# atmel_midi_cv_2layer.net
KiCad netlist of a schematic drawn in EAGLE
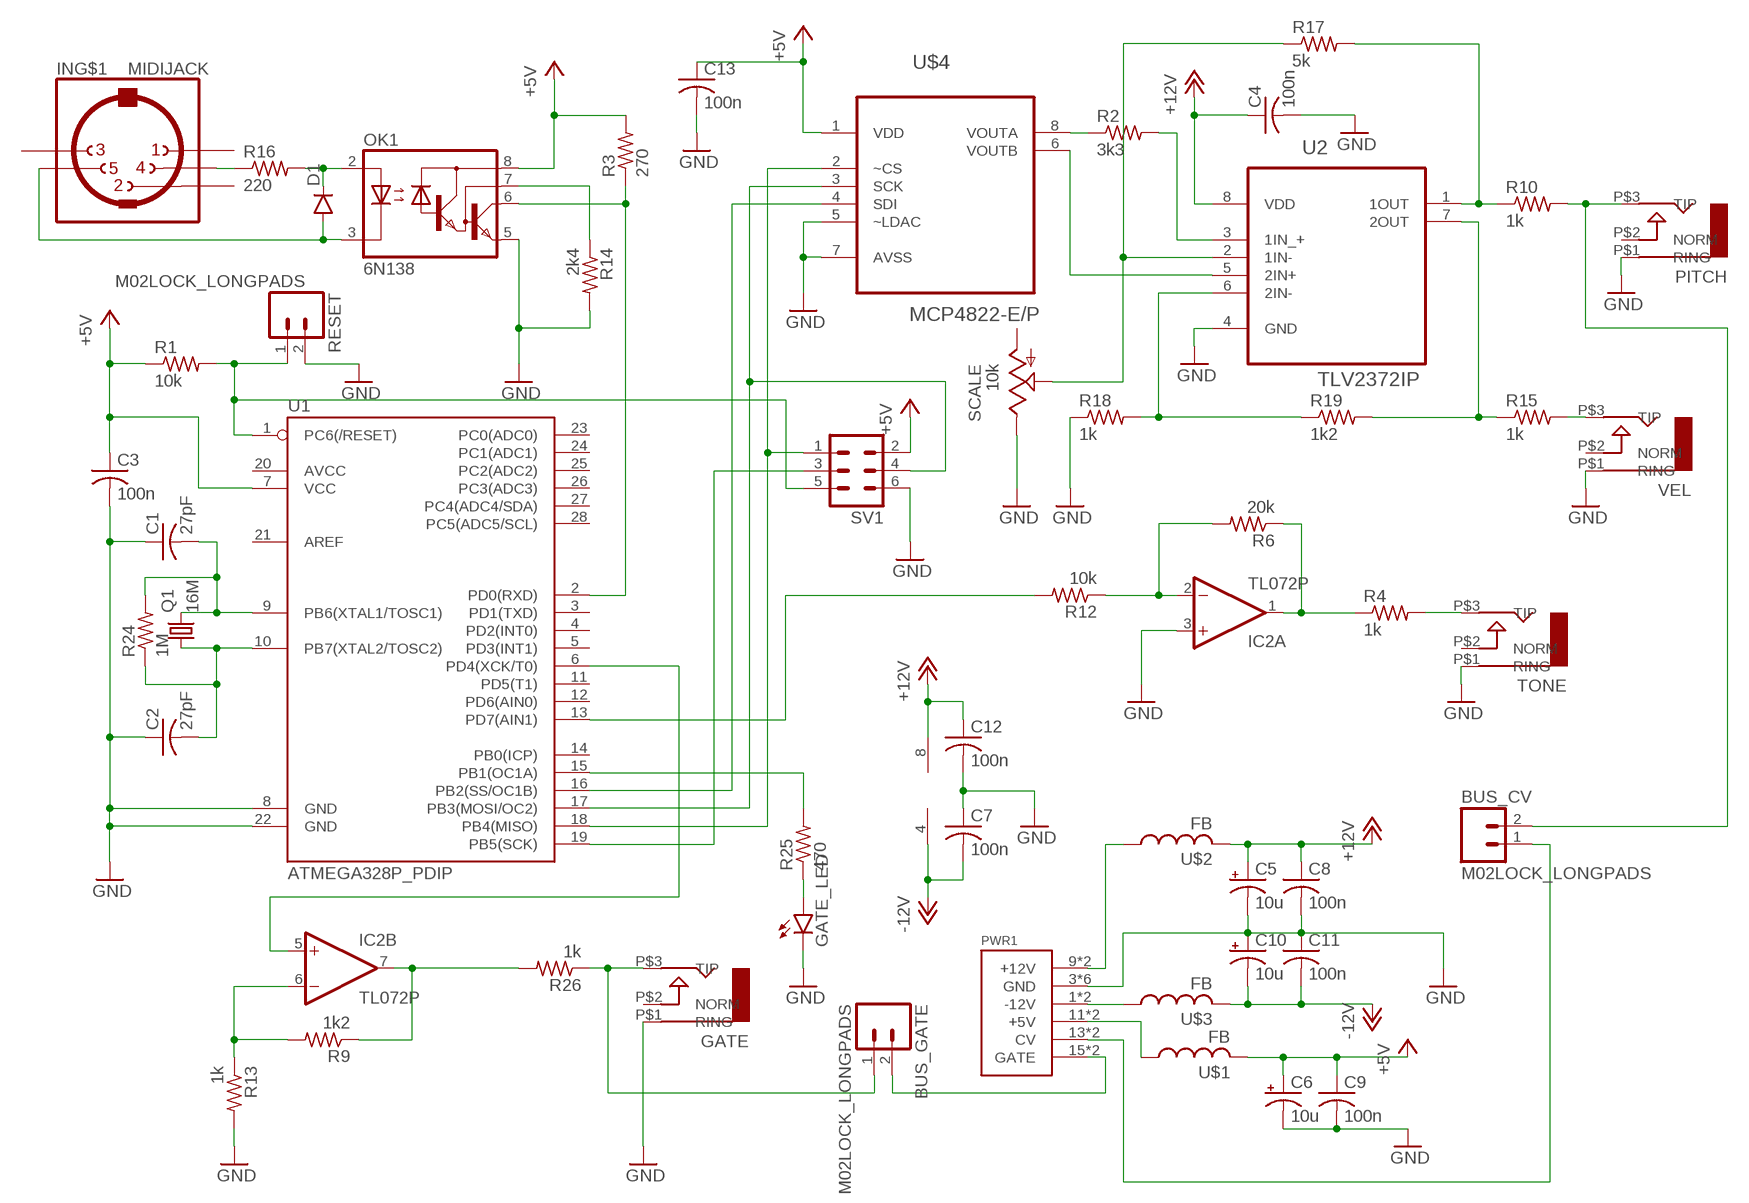
[diagram p0: schematic, sheet 1]

(export (version "E")
  (design (tool "Eeschema 10.0.6"))
  (components
    (comp (ref "BUS_CV")
      (value "M02LOCK_LONGPADS")
      (footprint "eagle-import:1X02_LOCK_LONGPADS")
      (libsource (lib "eagle-import") (part "M02LOCK_LONGPADS"))
    )
    (comp (ref "BUS_GATE")
      (value "M02LOCK_LONGPADS")
      (footprint "eagle-import:1X02_LOCK_LONGPADS")
      (libsource (lib "eagle-import") (part "M02LOCK_LONGPADS"))
    )
    (comp (ref "C1")
      (value "27pF")
      (footprint "eagle-import:C025-040X050")
      (libsource (lib "eagle-import") (part "C-US025-040X050"))
    )
    (comp (ref "C2")
      (value "27pF")
      (footprint "eagle-import:C025-040X050")
      (libsource (lib "eagle-import") (part "C-US025-040X050"))
    )
    (comp (ref "C3")
      (value "100n")
      (footprint "eagle-import:C050-024X044")
      (libsource (lib "eagle-import") (part "C-US050-024X044"))
    )
    (comp (ref "C4")
      (value "100n")
      (footprint "eagle-import:C050-024X044")
      (libsource (lib "eagle-import") (part "C-US050-024X044"))
    )
    (comp (ref "C5")
      (value "10u")
      (footprint "eagle-import:B45181A")
      (libsource (lib "eagle-import") (part "CPOL-USB45181A"))
    )
    (comp (ref "C6")
      (value "10u")
      (footprint "eagle-import:B45181A")
      (libsource (lib "eagle-import") (part "CPOL-USB45181A"))
    )
    (comp (ref "C7")
      (value "100n")
      (footprint "eagle-import:C050-024X044")
      (libsource (lib "eagle-import") (part "C-US050-024X044"))
    )
    (comp (ref "C8")
      (value "100n")
      (footprint "eagle-import:C050-024X044")
      (libsource (lib "eagle-import") (part "C-US050-024X044"))
    )
    (comp (ref "C9")
      (value "100n")
      (footprint "eagle-import:C050-024X044")
      (libsource (lib "eagle-import") (part "C-US050-024X044"))
    )
    (comp (ref "C10")
      (value "10u")
      (footprint "eagle-import:B45181A")
      (libsource (lib "eagle-import") (part "CPOL-USB45181A"))
    )
    (comp (ref "C11")
      (value "100n")
      (footprint "eagle-import:C050-024X044")
      (libsource (lib "eagle-import") (part "C-US050-024X044"))
    )
    (comp (ref "C12")
      (value "100n")
      (footprint "eagle-import:C050-024X044")
      (libsource (lib "eagle-import") (part "C-US050-024X044"))
    )
    (comp (ref "C13")
      (value "100n")
      (footprint "eagle-import:C050-024X044")
      (libsource (lib "eagle-import") (part "C-US050-024X044"))
    )
    (comp (ref "D1")
      (value "DIODE1N4148")
      (footprint "eagle-import:DIODE-1N4148")
      (libsource (lib "eagle-import") (part "DIODE1N4148"))
    )
    (comp (ref "GATE")
      (value "AUDIO-JACKITEAD")
      (footprint "eagle-import:JACK-90DEG-ITEAD")
      (libsource (lib "eagle-import") (part "AUDIO-JACKITEAD"))
    )
    (comp (ref "GATE_LED")
      (value "LED3MM")
      (footprint "eagle-import:LED3MM")
      (libsource (lib "eagle-import") (part "LED3MM"))
    )
    (comp (ref "IC2")
      (value "TL072P")
      (footprint "eagle-import:DIL08")
      (libsource (lib "eagle-import") (part "TL072P"))
    )
    (comp (ref "IN")
      (value "MIDIJACK")
      (footprint "eagle-import:CP-2350")
      (libsource (lib "eagle-import") (part "MIDIJACK"))
    )
    (comp (ref "OK1")
      (value "6N138")
      (footprint "eagle-import:DIL08")
      (fields (field (name "MF") "VISHAY/TELEFUNKEN"))
      (libsource (lib "eagle-import") (part "6N138"))
    )
    (comp (ref "PITCH")
      (value "AUDIO-JACKITEAD")
      (footprint "eagle-import:JACK-90DEG-ITEAD")
      (libsource (lib "eagle-import") (part "AUDIO-JACKITEAD"))
    )
    (comp (ref "PWR1")
      (value "POWER")
      (footprint "eagle-import:POWER_16")
      (libsource (lib "eagle-import") (part "POWER"))
    )
    (comp (ref "Q1")
      (value "16M")
      (footprint "eagle-import:HC49_S")
      (libsource (lib "eagle-import") (part "CRYSTALHC49S"))
    )
    (comp (ref "R1")
      (value "10k")
      (footprint "eagle-import:0207_7")
      (libsource (lib "eagle-import") (part "R-US_0207/7"))
    )
    (comp (ref "R2")
      (value "3k3")
      (footprint "eagle-import:0207_7")
      (libsource (lib "eagle-import") (part "R-US_0207/7"))
    )
    (comp (ref "R3")
      (value "270")
      (footprint "eagle-import:0207_7")
      (libsource (lib "eagle-import") (part "R-US_0207/7"))
    )
    (comp (ref "R4")
      (value "1k")
      (footprint "eagle-import:0207_7")
      (libsource (lib "eagle-import") (part "R-US_0207/7"))
    )
    (comp (ref "R6")
      (value "20k")
      (footprint "eagle-import:0207_7")
      (libsource (lib "eagle-import") (part "R-US_0207/7"))
    )
    (comp (ref "R9")
      (value "1k2")
      (footprint "eagle-import:0207_7")
      (libsource (lib "eagle-import") (part "R-US_0207/7"))
    )
    (comp (ref "R10")
      (value "1k")
      (footprint "eagle-import:0207_7")
      (libsource (lib "eagle-import") (part "R-US_0207/7"))
    )
    (comp (ref "R12")
      (value "10k")
      (footprint "eagle-import:0207_7")
      (libsource (lib "eagle-import") (part "R-US_0207/7"))
    )
    (comp (ref "R13")
      (value "1k")
      (footprint "eagle-import:0207_7")
      (libsource (lib "eagle-import") (part "R-US_0207/7"))
    )
    (comp (ref "R14")
      (value "2k4")
      (footprint "eagle-import:0207_7")
      (libsource (lib "eagle-import") (part "R-US_0207/7"))
    )
    (comp (ref "R15")
      (value "1k")
      (footprint "eagle-import:0207_7")
      (libsource (lib "eagle-import") (part "R-US_0207/7"))
    )
    (comp (ref "R16")
      (value "220")
      (footprint "eagle-import:0207_7")
      (libsource (lib "eagle-import") (part "R-US_0207/7"))
    )
    (comp (ref "R17")
      (value "5k")
      (footprint "eagle-import:0207_7")
      (libsource (lib "eagle-import") (part "R-US_0207/7"))
    )
    (comp (ref "R18")
      (value "1k")
      (footprint "eagle-import:0207_7")
      (libsource (lib "eagle-import") (part "R-US_0207/7"))
    )
    (comp (ref "R19")
      (value "1k2")
      (footprint "eagle-import:0207_7")
      (libsource (lib "eagle-import") (part "R-US_0207/7"))
    )
    (comp (ref "R24")
      (value "1M")
      (footprint "eagle-import:0207_7")
      (libsource (lib "eagle-import") (part "R-US_0207/7"))
    )
    (comp (ref "R25")
      (value "470")
      (footprint "eagle-import:0207_7")
      (libsource (lib "eagle-import") (part "R-US_0207/7"))
    )
    (comp (ref "R26")
      (value "1k")
      (footprint "eagle-import:0207_7")
      (libsource (lib "eagle-import") (part "R-US_0207/7"))
    )
    (comp (ref "RESET")
      (value "M02LOCK_LONGPADS")
      (footprint "eagle-import:1X02_LOCK_LONGPADS")
      (libsource (lib "eagle-import") (part "M02LOCK_LONGPADS"))
    )
    (comp (ref "SCALE")
      (value "10k")
      (footprint "eagle-import:B64W")
      (libsource (lib "eagle-import") (part "TRIM_US-B64W"))
    )
    (comp (ref "SV1")
      (value "MA03-2")
      (footprint "eagle-import:MA03-2")
      (libsource (lib "eagle-import") (part "MA03-2"))
    )
    (comp (ref "TONE")
      (value "AUDIO-JACKITEAD")
      (footprint "eagle-import:JACK-90DEG-ITEAD")
      (libsource (lib "eagle-import") (part "AUDIO-JACKITEAD"))
    )
    (comp (ref "U$1") (value "FB") (footprint "eagle-import:FB") (libsource (lib "eagle-import") (part "FB")))
    (comp (ref "U$2") (value "FB") (footprint "eagle-import:FB") (libsource (lib "eagle-import") (part "FB")))
    (comp (ref "U$3") (value "FB") (footprint "eagle-import:FB") (libsource (lib "eagle-import") (part "FB")))
    (comp (ref "U$4")
      (value "MCP4822-E/P")
      (footprint "eagle-import:DIP254P762X432-8")
      (libsource (lib "eagle-import") (part "MCP4822-E/P"))
    )
    (comp (ref "U1")
      (value "ATMEGA328P_PDIP")
      (footprint "eagle-import:DIL28-3")
      (libsource (lib "eagle-import") (part "ATMEGA328P_PDIP"))
    )
    (comp (ref "U2")
      (value "TLV2372IP")
      (footprint "eagle-import:DIP254P762X508-8")
      (libsource (lib "eagle-import") (part "TLV2372IP"))
    )
    (comp (ref "VEL")
      (value "AUDIO-JACKITEAD")
      (footprint "eagle-import:JACK-90DEG-ITEAD")
      (libsource (lib "eagle-import") (part "AUDIO-JACKITEAD"))
    )
  )
  (nets
    (net (code "1") (name "+5V") (class "Default")
      (node (ref "C13") (pin "1") (pinfunction "1_1") (pintype "passive"))
      (node (ref "C3") (pin "1") (pinfunction "1_1") (pintype "passive"))
      (node (ref "C6") (pin "+") (pinfunction "+_+") (pintype "passive"))
      (node (ref "C9") (pin "1") (pinfunction "1_1") (pintype "passive"))
      (node (ref "OK1") (pin "8") (pinfunction "VCC_8") (pintype "passive"))
      (node (ref "R1") (pin "1") (pinfunction "1_1") (pintype "passive"))
      (node (ref "R3") (pin "2") (pinfunction "2_2") (pintype "passive"))
      (node (ref "SV1") (pin "2") (pinfunction "2_2") (pintype "passive"))
      (node (ref "U$1") (pin "P$2") (pinfunction "2_P$2") (pintype "passive"))
      (node (ref "U$4") (pin "1") (pinfunction "VDD_1") (pintype "power_in"))
      (node (ref "U1") (pin "7") (pinfunction "VCC_7") (pintype "bidirectional"))
    )
    (net (code "2") (name "+12V") (class "Default")
      (node (ref "C12") (pin "1") (pinfunction "1_1") (pintype "passive"))
      (node (ref "C4") (pin "1") (pinfunction "1_1") (pintype "passive"))
      (node (ref "C5") (pin "+") (pinfunction "+_+") (pintype "passive"))
      (node (ref "C8") (pin "1") (pinfunction "1_1") (pintype "passive"))
      (node (ref "IC2") (pin "8") (pinfunction "V+_8") (pintype "power_in"))
      (node (ref "U$2") (pin "P$2") (pinfunction "2_P$2") (pintype "passive"))
      (node (ref "U2") (pin "8") (pinfunction "VDD_8") (pintype "power_in"))
    )
    (net (code "3") (name "-12V") (class "Default")
      (node (ref "C10") (pin "-") (pinfunction "-_-") (pintype "passive"))
      (node (ref "C11") (pin "2") (pinfunction "2_2") (pintype "passive"))
      (node (ref "C7") (pin "2") (pinfunction "2_2") (pintype "passive"))
      (node (ref "IC2") (pin "4") (pinfunction "V-_4") (pintype "power_in"))
      (node (ref "U$3") (pin "P$2") (pinfunction "2_P$2") (pintype "passive"))
    )
    (net (code "4") (name "GND") (class "Default")
      (node (ref "C1") (pin "1") (pinfunction "1_1") (pintype "passive"))
      (node (ref "C10") (pin "+") (pinfunction "+_+") (pintype "passive"))
      (node (ref "C11") (pin "1") (pinfunction "1_1") (pintype "passive"))
      (node (ref "C12") (pin "2") (pinfunction "2_2") (pintype "passive"))
      (node (ref "C13") (pin "2") (pinfunction "2_2") (pintype "passive"))
      (node (ref "C2") (pin "1") (pinfunction "1_1") (pintype "passive"))
      (node (ref "C3") (pin "2") (pinfunction "2_2") (pintype "passive"))
      (node (ref "C4") (pin "2") (pinfunction "2_2") (pintype "passive"))
      (node (ref "C5") (pin "-") (pinfunction "-_-") (pintype "passive"))
      (node (ref "C6") (pin "-") (pinfunction "-_-") (pintype "passive"))
      (node (ref "C7") (pin "1") (pinfunction "1_1") (pintype "passive"))
      (node (ref "C8") (pin "2") (pinfunction "2_2") (pintype "passive"))
      (node (ref "C9") (pin "2") (pinfunction "2_2") (pintype "passive"))
      (node (ref "GATE") (pin "P$1") (pinfunction "RING_P$1") (pintype "bidirectional"))
      (node (ref "GATE_LED") (pin "K") (pinfunction "C_K") (pintype "passive"))
      (node (ref "IC2") (pin "3") (pinfunction "+IN_3") (pintype "input"))
      (node (ref "OK1") (pin "5") (pinfunction "GND_5") (pintype "passive"))
      (node (ref "PITCH") (pin "P$1") (pinfunction "RING_P$1") (pintype "bidirectional"))
      (node (ref "PWR1") (pin "3") (pinfunction "GND_3") (pintype "bidirectional"))
      (node (ref "PWR1") (pin "4") (pinfunction "GND_4") (pintype "bidirectional"))
      (node (ref "PWR1") (pin "5") (pinfunction "GND_5") (pintype "bidirectional"))
      (node (ref "PWR1") (pin "6") (pinfunction "GND_6") (pintype "bidirectional"))
      (node (ref "PWR1") (pin "7") (pinfunction "GND_7") (pintype "bidirectional"))
      (node (ref "PWR1") (pin "8") (pinfunction "GND_8") (pintype "bidirectional"))
      (node (ref "R13") (pin "2") (pinfunction "2_2") (pintype "passive"))
      (node (ref "R14") (pin "2") (pinfunction "2_2") (pintype "passive"))
      (node (ref "R18") (pin "1") (pinfunction "1_1") (pintype "passive"))
      (node (ref "RESET") (pin "2") (pinfunction "2_2") (pintype "passive"))
      (node (ref "SCALE") (pin "E") (pinfunction "E_E") (pintype "passive"))
      (node (ref "SV1") (pin "6") (pinfunction "6_6") (pintype "passive"))
      (node (ref "TONE") (pin "P$1") (pinfunction "RING_P$1") (pintype "bidirectional"))
      (node (ref "U$4") (pin "5") (pinfunction "~{LDAC}_5") (pintype "input"))
      (node (ref "U$4") (pin "7") (pinfunction "AVSS_7") (pintype "passive"))
      (node (ref "U1") (pin "22") (pinfunction "GND_22") (pintype "bidirectional"))
      (node (ref "U1") (pin "8") (pinfunction "GND_8") (pintype "bidirectional"))
      (node (ref "U2") (pin "4") (pinfunction "GND_4") (pintype "passive"))
      (node (ref "VEL") (pin "P$1") (pinfunction "RING_P$1") (pintype "bidirectional"))
    )
    (net (code "5") (name "Net-(BUS_CV-Pad1)") (class "Default")
      (node (ref "BUS_CV") (pin "1") (pinfunction "1_1") (pintype "passive"))
      (node (ref "PWR1") (pin "13") (pinfunction "CV_13") (pintype "bidirectional"))
      (node (ref "PWR1") (pin "14") (pinfunction "CV_14") (pintype "bidirectional"))
    )
    (net (code "6") (name "Net-(BUS_GATE-Pad2)") (class "Default")
      (node (ref "BUS_GATE") (pin "2") (pinfunction "2_2") (pintype "passive"))
      (node (ref "PWR1") (pin "15") (pinfunction "GATE_15") (pintype "bidirectional"))
      (node (ref "PWR1") (pin "16") (pinfunction "GATE_16") (pintype "bidirectional"))
    )
    (net (code "7") (name "Net-(GATE-TIP)") (class "Default")
      (node (ref "BUS_GATE") (pin "1") (pinfunction "1_1") (pintype "passive"))
      (node (ref "GATE") (pin "P$3") (pinfunction "TIP_P$3") (pintype "bidirectional"))
      (node (ref "R26") (pin "1") (pinfunction "1_1") (pintype "passive"))
    )
    (net (code "8") (name "Net-(GATE_LED-PadA)") (class "Default")
      (node (ref "GATE_LED") (pin "A") (pinfunction "A_A") (pintype "passive"))
      (node (ref "R25") (pin "1") (pinfunction "1_1") (pintype "passive"))
    )
    (net (code "9") (name "Net-(IC2A--IN)") (class "Default")
      (node (ref "IC2") (pin "2") (pinfunction "-IN_2") (pintype "input"))
      (node (ref "R12") (pin "1") (pinfunction "1_1") (pintype "passive"))
      (node (ref "R6") (pin "2") (pinfunction "2_2") (pintype "passive"))
    )
    (net (code "10") (name "Net-(IC2A-OUT)") (class "Default")
      (node (ref "IC2") (pin "1") (pinfunction "OUT_1") (pintype "output"))
      (node (ref "R4") (pin "1") (pinfunction "1_1") (pintype "passive"))
      (node (ref "R6") (pin "1") (pinfunction "1_1") (pintype "passive"))
    )
    (net (code "11") (name "Net-(IC2B-+IN)") (class "Default")
      (node (ref "IC2") (pin "5") (pinfunction "+IN_5") (pintype "input"))
      (node (ref "U1") (pin "6") (pinfunction "PD4(XCK/T0)_6") (pintype "bidirectional"))
    )
    (net (code "12") (name "Net-(IC2B--IN)") (class "Default")
      (node (ref "IC2") (pin "6") (pinfunction "-IN_6") (pintype "input"))
      (node (ref "R13") (pin "1") (pinfunction "1_1") (pintype "passive"))
      (node (ref "R9") (pin "2") (pinfunction "2_2") (pintype "passive"))
    )
    (net (code "13") (name "Net-(IC2B-OUT)") (class "Default")
      (node (ref "IC2") (pin "7") (pinfunction "OUT_7") (pintype "output"))
      (node (ref "R26") (pin "2") (pinfunction "2_2") (pintype "passive"))
      (node (ref "R9") (pin "1") (pinfunction "1_1") (pintype "passive"))
    )
    (net (code "14") (name "Net-(IN-Pad4)") (class "Default")
      (node (ref "IN") (pin "4") (pinfunction "4_4") (pintype "passive"))
      (node (ref "R16") (pin "1") (pinfunction "1_1") (pintype "passive"))
    )
    (net (code "15") (name "Net-(OK1-A)") (class "Default")
      (node (ref "D1") (pin "C") (pinfunction "C_C") (pintype "passive"))
      (node (ref "OK1") (pin "2") (pinfunction "A_2") (pintype "passive"))
      (node (ref "R16") (pin "2") (pinfunction "2_2") (pintype "passive"))
    )
    (net (code "16") (name "Net-(OK1-C)") (class "Default")
      (node (ref "D1") (pin "A") (pinfunction "A_A") (pintype "passive"))
      (node (ref "IN") (pin "5") (pinfunction "5_5") (pintype "passive"))
      (node (ref "OK1") (pin "3") (pinfunction "C_3") (pintype "passive"))
    )
    (net (code "17") (name "Net-(OK1-VB)") (class "Default")
      (node (ref "OK1") (pin "7") (pinfunction "VB_7") (pintype "passive"))
      (node (ref "R14") (pin "1") (pinfunction "1_1") (pintype "passive"))
    )
    (net (code "18") (name "Net-(OK1-VO)") (class "Default")
      (node (ref "OK1") (pin "6") (pinfunction "VO_6") (pintype "passive"))
      (node (ref "R3") (pin "1") (pinfunction "1_1") (pintype "passive"))
      (node (ref "U1") (pin "2") (pinfunction "PD0(RXD)_2") (pintype "bidirectional"))
    )
    (net (code "19") (name "Net-(PITCH-TIP)") (class "Default")
      (node (ref "BUS_CV") (pin "2") (pinfunction "2_2") (pintype "passive"))
      (node (ref "PITCH") (pin "P$3") (pinfunction "TIP_P$3") (pintype "bidirectional"))
      (node (ref "R10") (pin "2") (pinfunction "2_2") (pintype "passive"))
    )
    (net (code "20") (name "Net-(TONE-TIP)") (class "Default")
      (node (ref "R4") (pin "2") (pinfunction "2_2") (pintype "passive"))
      (node (ref "TONE") (pin "P$3") (pinfunction "TIP_P$3") (pintype "bidirectional"))
    )
    (net (code "21") (name "Net-(U$1-1)") (class "Default")
      (node (ref "PWR1") (pin "11") (pinfunction "+5V_11") (pintype "bidirectional"))
      (node (ref "PWR1") (pin "12") (pinfunction "+5V_12") (pintype "bidirectional"))
      (node (ref "U$1") (pin "P$1") (pinfunction "1_P$1") (pintype "passive"))
    )
    (net (code "22") (name "Net-(U$2-1)") (class "Default")
      (node (ref "PWR1") (pin "10") (pinfunction "+12V_10") (pintype "bidirectional"))
      (node (ref "PWR1") (pin "9") (pinfunction "+12V_9") (pintype "bidirectional"))
      (node (ref "U$2") (pin "P$1") (pinfunction "1_P$1") (pintype "passive"))
    )
    (net (code "23") (name "Net-(U$3-1)") (class "Default")
      (node (ref "PWR1") (pin "1") (pinfunction "-12V_1") (pintype "bidirectional"))
      (node (ref "PWR1") (pin "2") (pinfunction "-12V_2") (pintype "bidirectional"))
      (node (ref "U$3") (pin "P$1") (pinfunction "1_P$1") (pintype "passive"))
    )
    (net (code "24") (name "Net-(U$4-SCK)") (class "Default")
      (node (ref "SV1") (pin "4") (pinfunction "4_4") (pintype "passive"))
      (node (ref "U$4") (pin "3") (pinfunction "SCK_3") (pintype "input"))
      (node (ref "U1") (pin "17") (pinfunction "PB3(MOSI/OC2)_17") (pintype "bidirectional"))
    )
    (net (code "25") (name "Net-(U$4-SDI)") (class "Default")
      (node (ref "U$4") (pin "4") (pinfunction "SDI_4") (pintype "input"))
      (node (ref "U1") (pin "16") (pinfunction "PB2(SS/OC1B)_16") (pintype "bidirectional"))
    )
    (net (code "26") (name "Net-(U$4-VOUTA)") (class "Default")
      (node (ref "R2") (pin "1") (pinfunction "1_1") (pintype "passive"))
      (node (ref "U$4") (pin "8") (pinfunction "VOUTA_8") (pintype "output"))
    )
    (net (code "27") (name "Net-(U$4-VOUTB)") (class "Default")
      (node (ref "U$4") (pin "6") (pinfunction "VOUTB_6") (pintype "output"))
      (node (ref "U2") (pin "5") (pinfunction "2IN+_5") (pintype "input"))
    )
    (net (code "28") (name "Net-(U$4-~{CS})") (class "Default")
      (node (ref "SV1") (pin "1") (pinfunction "1_1") (pintype "passive"))
      (node (ref "U$4") (pin "2") (pinfunction "~{CS}_2") (pintype "input"))
      (node (ref "U1") (pin "18") (pinfunction "PB4(MISO)_18") (pintype "bidirectional"))
    )
    (net (code "29") (name "Net-(U1-PB1(OC1A))") (class "Default")
      (node (ref "R25") (pin "2") (pinfunction "2_2") (pintype "passive"))
      (node (ref "U1") (pin "15") (pinfunction "PB1(OC1A)_15") (pintype "bidirectional"))
    )
    (net (code "30") (name "Net-(U1-PB5(SCK))") (class "Default")
      (node (ref "SV1") (pin "3") (pinfunction "3_3") (pintype "passive"))
      (node (ref "U1") (pin "19") (pinfunction "PB5(SCK)_19") (pintype "bidirectional"))
    )
    (net (code "31") (name "Net-(U1-PB6(XTAL1{slash}TOSC1))") (class "Default")
      (node (ref "C1") (pin "2") (pinfunction "2_2") (pintype "passive"))
      (node (ref "Q1") (pin "2") (pinfunction "2_2") (pintype "passive"))
      (node (ref "R24") (pin "2") (pinfunction "2_2") (pintype "passive"))
      (node (ref "U1") (pin "9") (pinfunction "PB6(XTAL1/TOSC1)_9") (pintype "bidirectional"))
    )
    (net (code "32") (name "Net-(U1-PB7(XTAL2{slash}TOSC2))") (class "Default")
      (node (ref "C2") (pin "2") (pinfunction "2_2") (pintype "passive"))
      (node (ref "Q1") (pin "1") (pinfunction "1_1") (pintype "passive"))
      (node (ref "R24") (pin "1") (pinfunction "1_1") (pintype "passive"))
      (node (ref "U1") (pin "10") (pinfunction "PB7(XTAL2/TOSC2)_10") (pintype "bidirectional"))
    )
    (net (code "33") (name "Net-(U1-PC6({slash}RESET))") (class "Default")
      (node (ref "R1") (pin "2") (pinfunction "2_2") (pintype "passive"))
      (node (ref "RESET") (pin "1") (pinfunction "1_1") (pintype "passive"))
      (node (ref "SV1") (pin "5") (pinfunction "5_5") (pintype "passive"))
      (node (ref "U1") (pin "1") (pinfunction "PC6(/RESET)_1") (pintype "bidirectional"))
    )
    (net (code "34") (name "Net-(U1-PD7(AIN1))") (class "Default")
      (node (ref "R12") (pin "2") (pinfunction "2_2") (pintype "passive"))
      (node (ref "U1") (pin "13") (pinfunction "PD7(AIN1)_13") (pintype "bidirectional"))
    )
    (net (code "35") (name "Net-(U2-1IN-)") (class "Default")
      (node (ref "R17") (pin "1") (pinfunction "1_1") (pintype "passive"))
      (node (ref "SCALE") (pin "P$1") (pinfunction "S_P$1") (pintype "passive"))
      (node (ref "SCALE") (pin "S") (pinfunction "S_S") (pintype "passive"))
      (node (ref "U2") (pin "2") (pinfunction "1IN-_2") (pintype "input"))
    )
    (net (code "36") (name "Net-(U2-1IN_+)") (class "Default")
      (node (ref "R2") (pin "2") (pinfunction "2_2") (pintype "passive"))
      (node (ref "U2") (pin "3") (pinfunction "1IN_+_3") (pintype "input"))
    )
    (net (code "37") (name "Net-(U2-1OUT)") (class "Default")
      (node (ref "R10") (pin "1") (pinfunction "1_1") (pintype "passive"))
      (node (ref "R17") (pin "2") (pinfunction "2_2") (pintype "passive"))
      (node (ref "U2") (pin "1") (pinfunction "1OUT_1") (pintype "output"))
    )
    (net (code "38") (name "Net-(U2-2IN-)") (class "Default")
      (node (ref "R18") (pin "2") (pinfunction "2_2") (pintype "passive"))
      (node (ref "R19") (pin "1") (pinfunction "1_1") (pintype "passive"))
      (node (ref "U2") (pin "6") (pinfunction "2IN-_6") (pintype "input"))
    )
    (net (code "39") (name "Net-(U2-2OUT)") (class "Default")
      (node (ref "R15") (pin "1") (pinfunction "1_1") (pintype "passive"))
      (node (ref "R19") (pin "2") (pinfunction "2_2") (pintype "passive"))
      (node (ref "U2") (pin "7") (pinfunction "2OUT_7") (pintype "output"))
    )
    (net (code "40") (name "Net-(VEL-TIP)") (class "Default")
      (node (ref "R15") (pin "2") (pinfunction "2_2") (pintype "passive"))
      (node (ref "VEL") (pin "P$3") (pinfunction "TIP_P$3") (pintype "bidirectional"))
    )
    (net (code "41") (name "unconnected-(GATE-NORM-PadP$2)") (class "Default")
      (node (ref "GATE") (pin "P$2") (pinfunction "NORM_P$2") (pintype "bidirectional"))
    )
    (net (code "42") (name "unconnected-(IN-Pad1)") (class "Default")
      (node (ref "IN") (pin "1") (pinfunction "1_1") (pintype "passive"))
    )
    (net (code "43") (name "unconnected-(IN-Pad2)") (class "Default")
      (node (ref "IN") (pin "2") (pinfunction "2_2") (pintype "passive"))
    )
    (net (code "44") (name "unconnected-(IN-Pad3)") (class "Default")
      (node (ref "IN") (pin "3") (pinfunction "3_3") (pintype "passive"))
    )
    (net (code "45") (name "unconnected-(PITCH-NORM-PadP$2)") (class "Default")
      (node (ref "PITCH") (pin "P$2") (pinfunction "NORM_P$2") (pintype "bidirectional"))
    )
    (net (code "46") (name "unconnected-(SCALE-PadA)") (class "Default")
      (node (ref "SCALE") (pin "A") (pinfunction "A_A") (pintype "passive"))
    )
    (net (code "47") (name "unconnected-(TONE-NORM-PadP$2)") (class "Default")
      (node (ref "TONE") (pin "P$2") (pinfunction "NORM_P$2") (pintype "bidirectional"))
    )
    (net (code "48") (name "unconnected-(U1-AREF-Pad21)") (class "Default")
      (node (ref "U1") (pin "21") (pinfunction "AREF_21") (pintype "bidirectional"))
    )
    (net (code "49") (name "unconnected-(U1-AVCC-Pad20)") (class "Default")
      (node (ref "U1") (pin "20") (pinfunction "AVCC_20") (pintype "bidirectional"))
    )
    (net (code "50") (name "unconnected-(U1-PB0(ICP)-Pad14)") (class "Default")
      (node (ref "U1") (pin "14") (pinfunction "PB0(ICP)_14") (pintype "bidirectional"))
    )
    (net (code "51") (name "unconnected-(U1-PC0(ADC0)-Pad23)") (class "Default")
      (node (ref "U1") (pin "23") (pinfunction "PC0(ADC0)_23") (pintype "bidirectional"))
    )
    (net (code "52") (name "unconnected-(U1-PC1(ADC1)-Pad24)") (class "Default")
      (node (ref "U1") (pin "24") (pinfunction "PC1(ADC1)_24") (pintype "bidirectional"))
    )
    (net (code "53") (name "unconnected-(U1-PC2(ADC2)-Pad25)") (class "Default")
      (node (ref "U1") (pin "25") (pinfunction "PC2(ADC2)_25") (pintype "bidirectional"))
    )
    (net (code "54") (name "unconnected-(U1-PC3(ADC3)-Pad26)") (class "Default")
      (node (ref "U1") (pin "26") (pinfunction "PC3(ADC3)_26") (pintype "bidirectional"))
    )
    (net (code "55") (name "unconnected-(U1-PC4(ADC4{slash}SDA)-Pad27)") (class "Default")
      (node (ref "U1") (pin "27") (pinfunction "PC4(ADC4/SDA)_27") (pintype "bidirectional"))
    )
    (net (code "56") (name "unconnected-(U1-PC5(ADC5{slash}SCL)-Pad28)") (class "Default")
      (node (ref "U1") (pin "28") (pinfunction "PC5(ADC5/SCL)_28") (pintype "bidirectional"))
    )
    (net (code "57") (name "unconnected-(U1-PD1(TXD)-Pad3)") (class "Default")
      (node (ref "U1") (pin "3") (pinfunction "PD1(TXD)_3") (pintype "bidirectional"))
    )
    (net (code "58") (name "unconnected-(U1-PD2(INT0)-Pad4)") (class "Default")
      (node (ref "U1") (pin "4") (pinfunction "PD2(INT0)_4") (pintype "bidirectional"))
    )
    (net (code "59") (name "unconnected-(U1-PD3(INT1)-Pad5)") (class "Default")
      (node (ref "U1") (pin "5") (pinfunction "PD3(INT1)_5") (pintype "bidirectional"))
    )
    (net (code "60") (name "unconnected-(U1-PD5(T1)-Pad11)") (class "Default")
      (node (ref "U1") (pin "11") (pinfunction "PD5(T1)_11") (pintype "bidirectional"))
    )
    (net (code "61") (name "unconnected-(U1-PD6(AIN0)-Pad12)") (class "Default")
      (node (ref "U1") (pin "12") (pinfunction "PD6(AIN0)_12") (pintype "bidirectional"))
    )
    (net (code "62") (name "unconnected-(VEL-NORM-PadP$2)") (class "Default")
      (node (ref "VEL") (pin "P$2") (pinfunction "NORM_P$2") (pintype "bidirectional"))
    )
  )
)
